# doogie_board.net
KiCad netlist of a schematic drawn in EAGLE
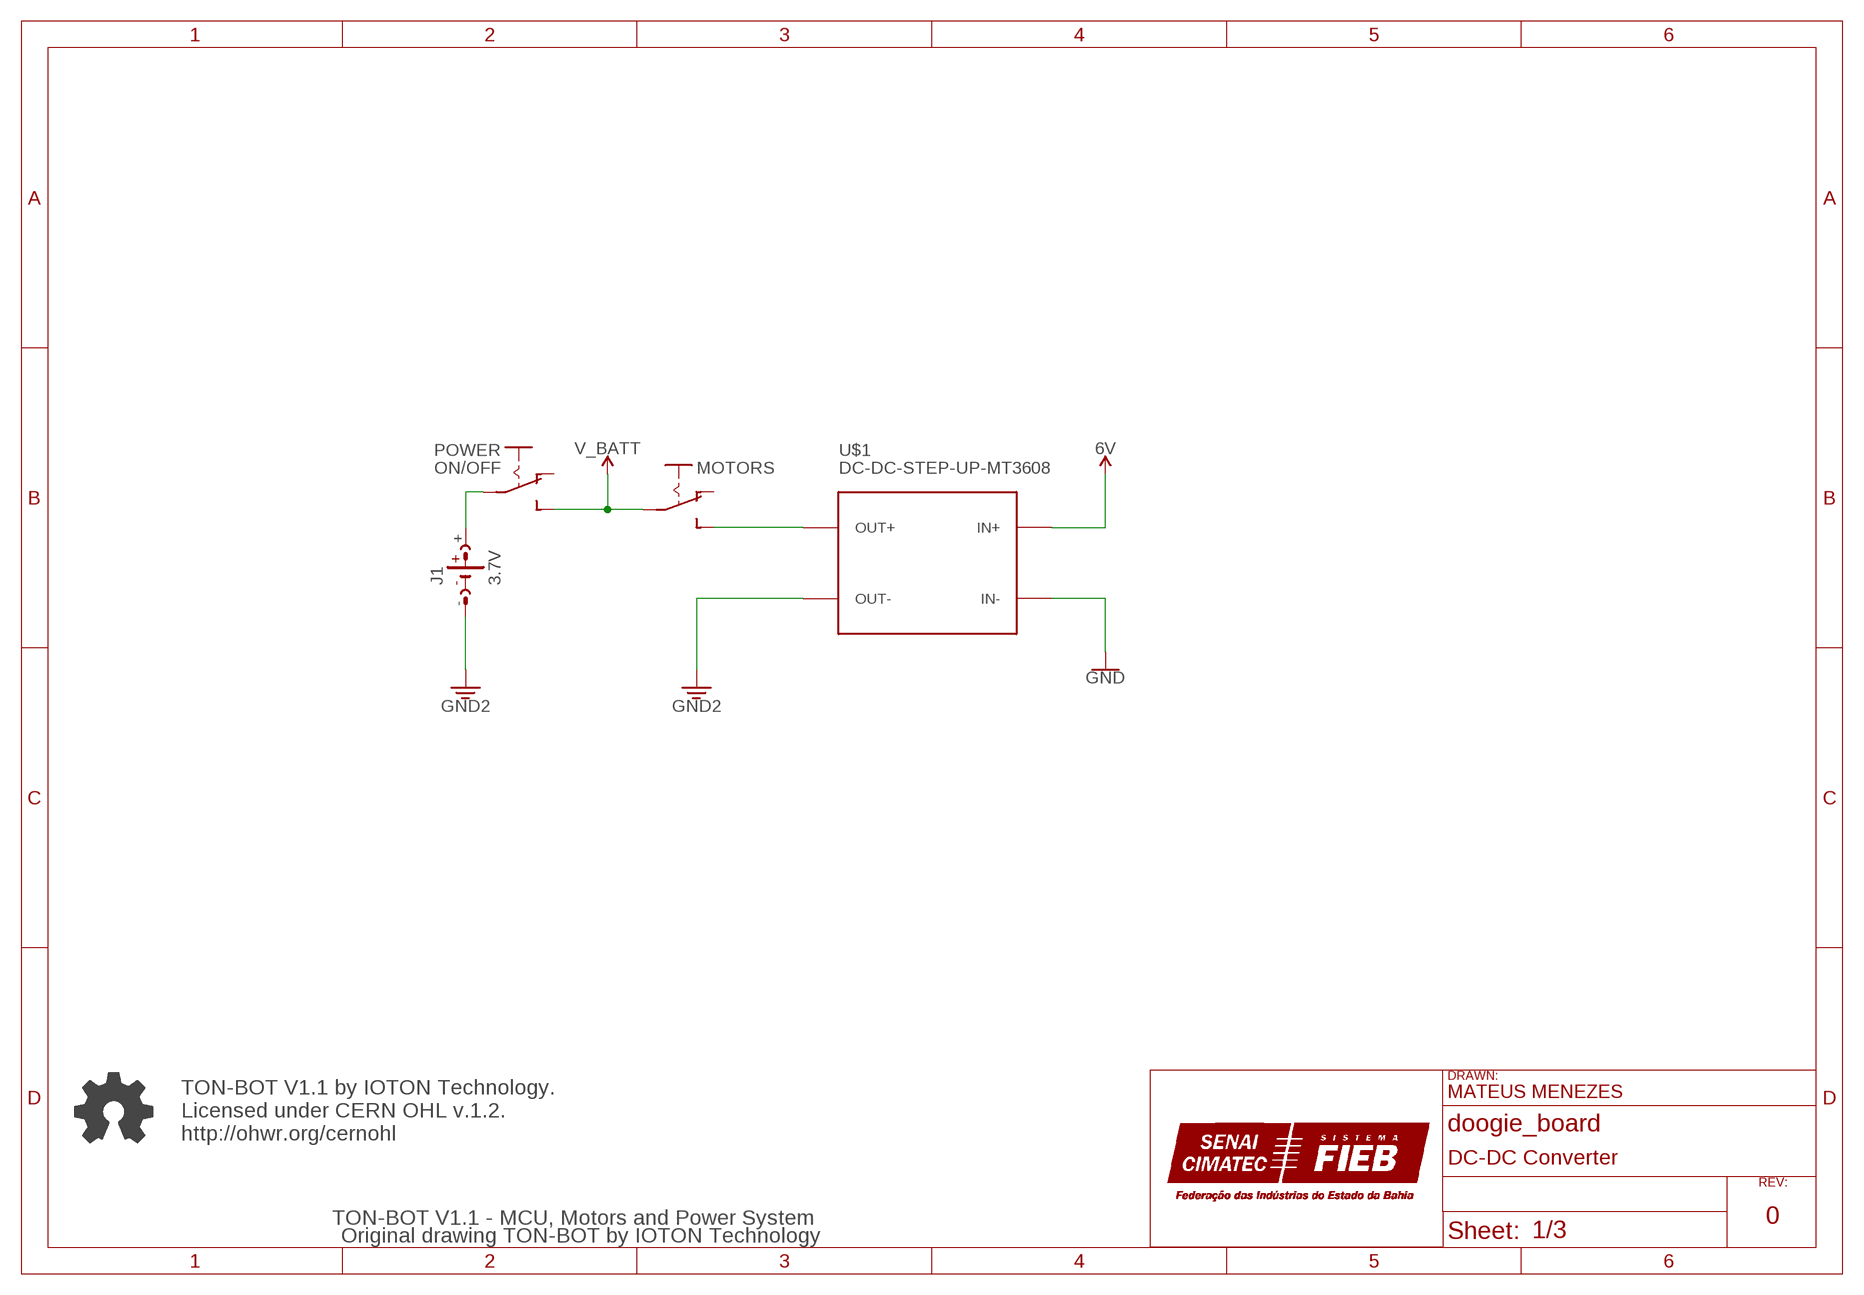
[diagram p0: schematic, sheet 1]
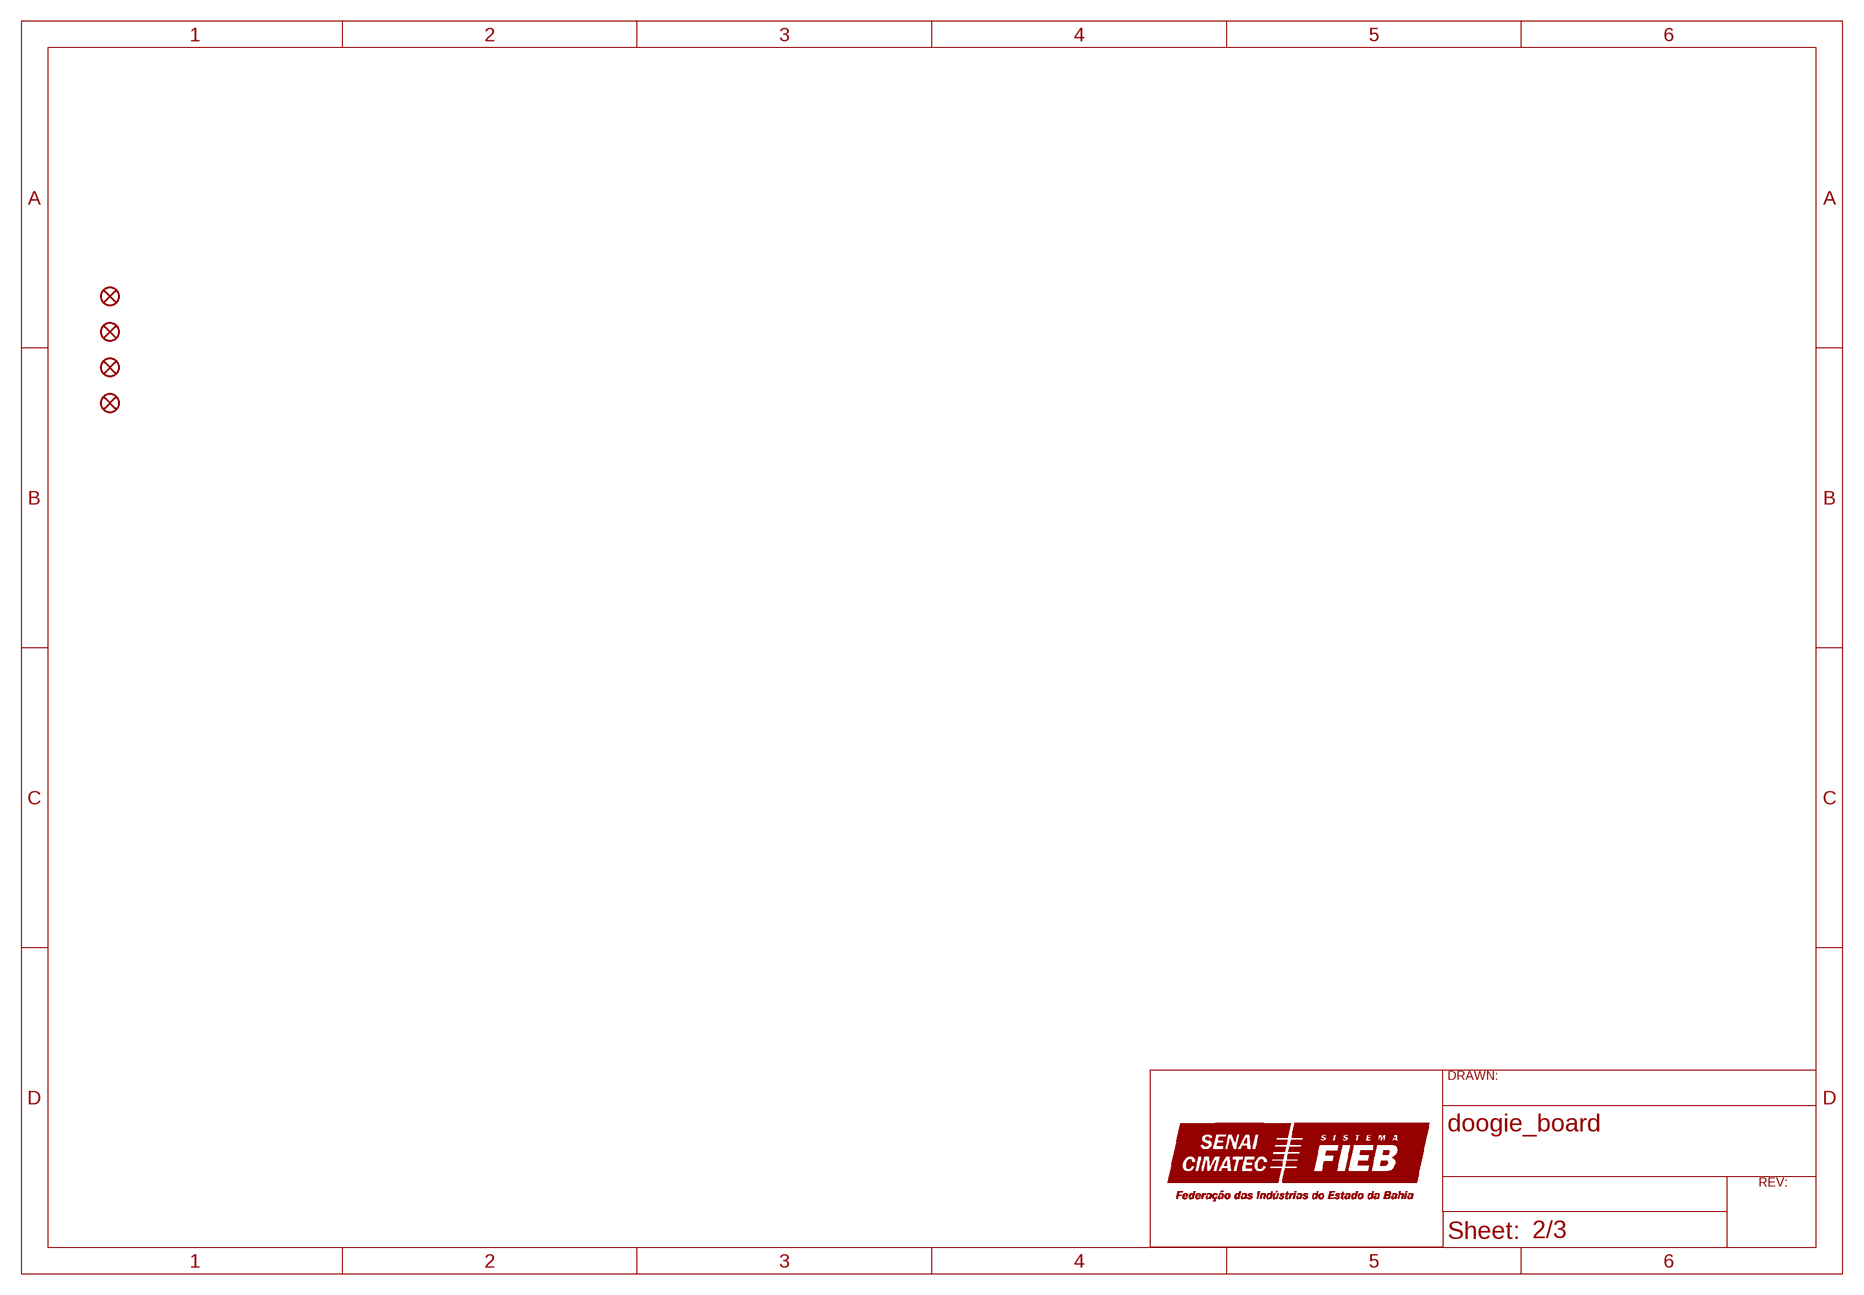
[diagram p1: schematic, sheet 2]
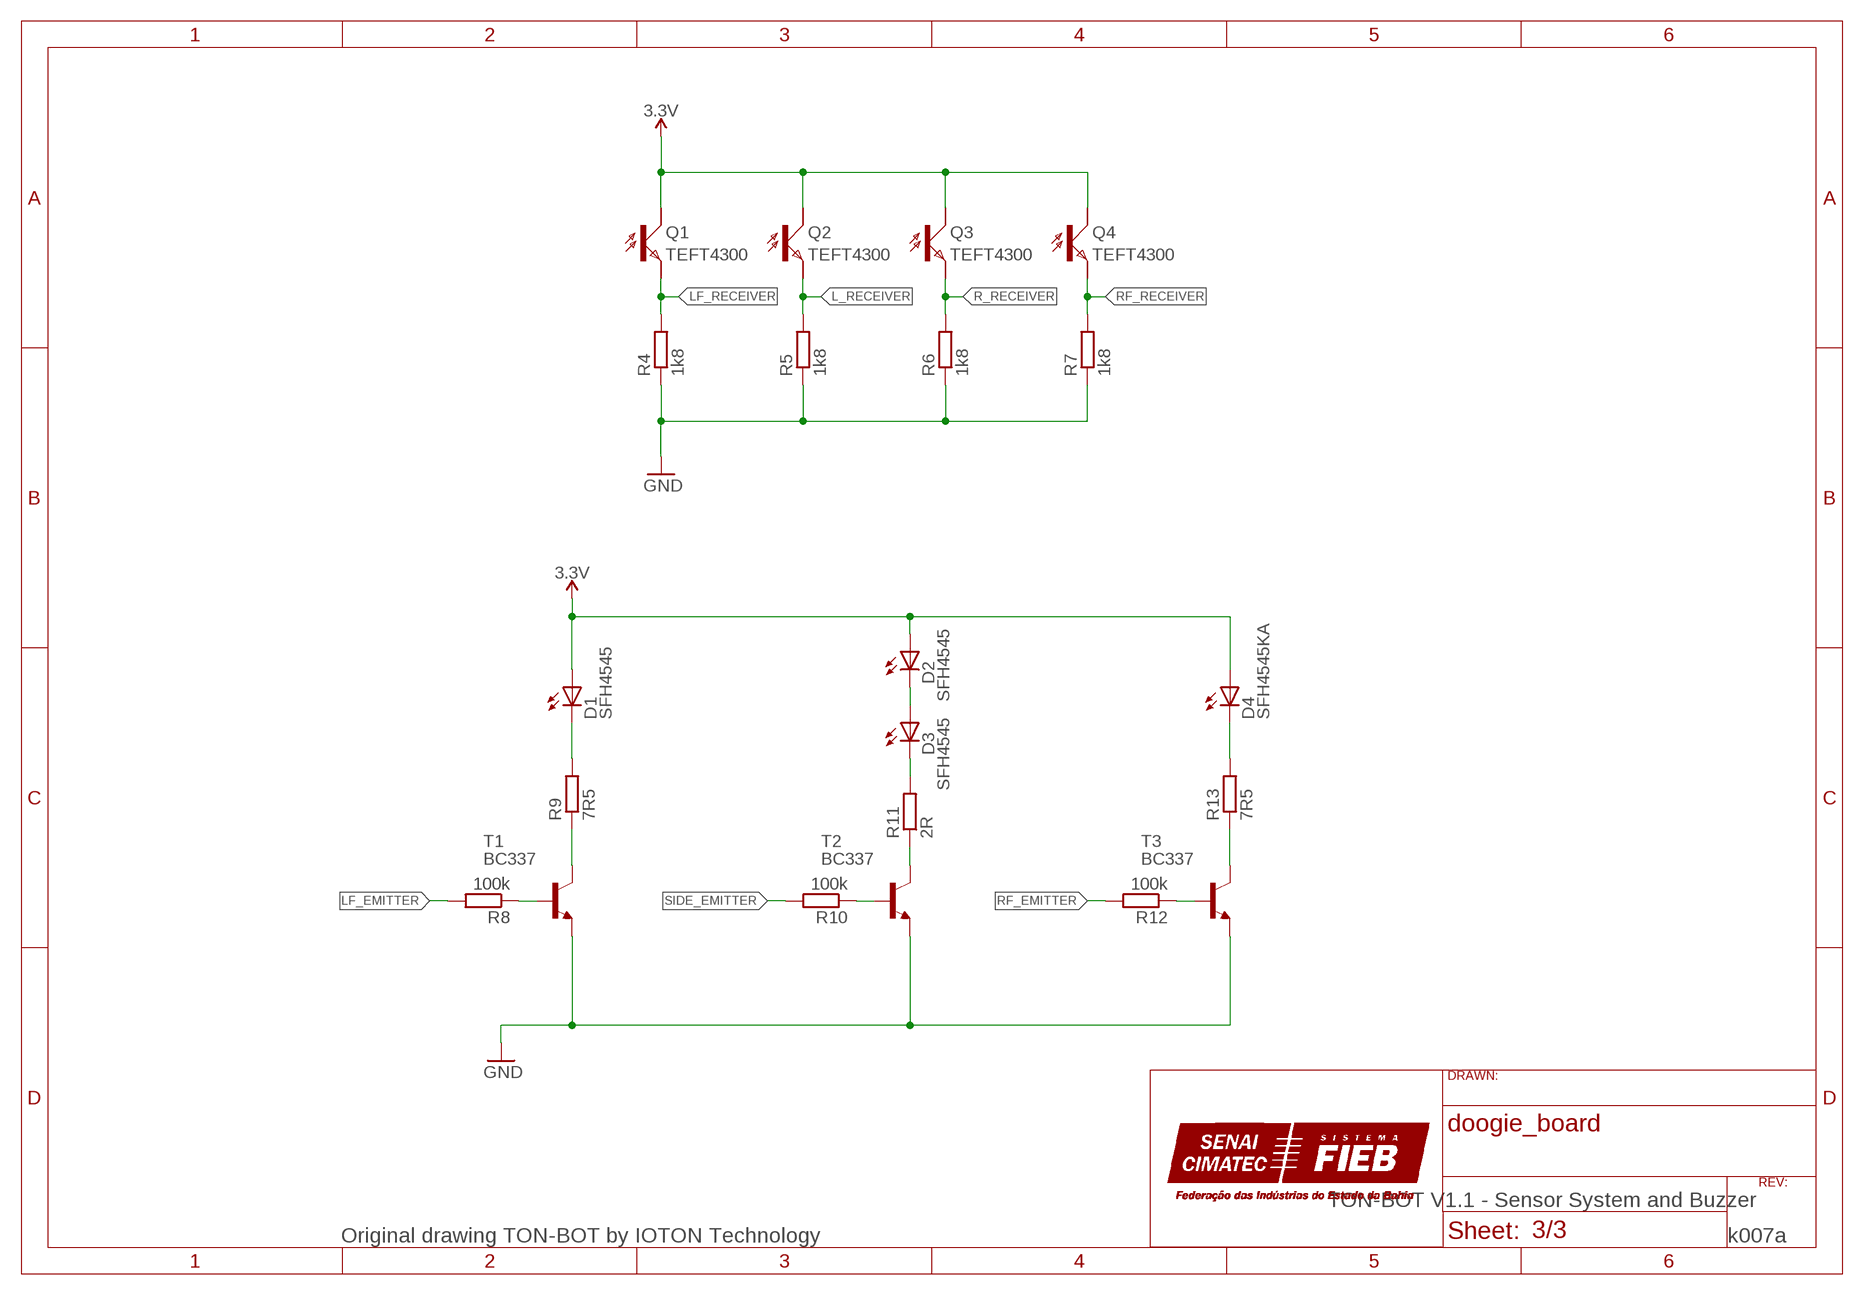
[diagram p2: schematic, sheet 3]

(export (version "E")
  (design (tool "Eeschema 10.0.6"))
  (components
    (comp (ref "JP1")
      (value "FIDUCIAL1X2")
      (footprint "eagle-import:FIDUCIAL-1X2")
      (libsource (lib "eagle-import") (part "FIDUCIAL1X2"))
    )
    (comp (ref "JP2")
      (value "FIDUCIAL1X2")
      (footprint "eagle-import:FIDUCIAL-1X2")
      (libsource (lib "eagle-import") (part "FIDUCIAL1X2"))
    )
    (comp (ref "JP3")
      (value "FIDUCIAL1X2")
      (footprint "eagle-import:FIDUCIAL-1X2")
      (libsource (lib "eagle-import") (part "FIDUCIAL1X2"))
    )
    (comp (ref "JP4")
      (value "FIDUCIAL1X2")
      (footprint "eagle-import:FIDUCIAL-1X2")
      (libsource (lib "eagle-import") (part "FIDUCIAL1X2"))
    )
    (comp (ref "U$3")
      (value "FRAME_A4P")
      (footprint "eagle-import:FRAME_A4P")
      (libsource (lib "eagle-import") (part "FRAME_A4P"))
    )
    (comp (ref "J1")
      (value "3.7V")
      (footprint "eagle-import:BATTERY")
      (libsource (lib "eagle-import") (part "BATTERY"))
    )
    (comp (ref "MOTORS")
      (value "SWITCHS")
      (footprint "eagle-import:SWITCH")
      (libsource (lib "eagle-import") (part "SWITCHS"))
    )
    (comp (ref "POWER")
      (value "ON/OFF")
      (footprint "eagle-import:SWITCH")
      (libsource (lib "eagle-import") (part "SWITCHS"))
    )
    (comp (ref "U$1")
      (value "DC-DC-STEP-UP-MT3608")
      (footprint "eagle-import:DC-DC-STEP-UP-MT3608")
      (libsource (lib "eagle-import") (part "DC-DC-STEP-UP-MT3608"))
    )
    (comp (ref "U$2")
      (value "FRAME_A4P")
      (footprint "eagle-import:FRAME_A4P")
      (fields
        (field (name "DESIGNER_NAME") "MATEUS MENEZES")
        (field (name "PAGE_DESCRIPTION") "DC-DC Converter")
        (field (name "REV_NUMBER") "0")
      )
      (libsource (lib "eagle-import") (part "FRAME_A4P"))
    )
    (comp (ref "D1")
      (value "SFH4545")
      (footprint "eagle-import:SFH4545-AK")
      (libsource (lib "eagle-import") (part "SFH4545AK"))
    )
    (comp (ref "D2")
      (value "SFH4545")
      (footprint "eagle-import:SFH4545-KA")
      (libsource (lib "eagle-import") (part "SFH4545KA"))
    )
    (comp (ref "D3")
      (value "SFH4545")
      (footprint "eagle-import:SFH4545-KA")
      (libsource (lib "eagle-import") (part "SFH4545KA"))
    )
    (comp (ref "D4")
      (value "SFH4545KA")
      (footprint "eagle-import:SFH4545-KA")
      (libsource (lib "eagle-import") (part "SFH4545KA"))
    )
    (comp (ref "Q1")
      (value "TEFT4300")
      (footprint "eagle-import:TEFT4300-CE")
      (libsource (lib "eagle-import") (part "TEFT4300CE"))
    )
    (comp (ref "Q2")
      (value "TEFT4300")
      (footprint "eagle-import:TEFT4300-EC")
      (libsource (lib "eagle-import") (part "TEFT4300EC"))
    )
    (comp (ref "Q3")
      (value "TEFT4300")
      (footprint "eagle-import:TEFT4300-CE")
      (libsource (lib "eagle-import") (part "TEFT4300CE"))
    )
    (comp (ref "Q4")
      (value "TEFT4300")
      (footprint "eagle-import:TEFT4300-EC")
      (libsource (lib "eagle-import") (part "TEFT4300EC"))
    )
    (comp (ref "R4")
      (value "1k8")
      (footprint "eagle-import:0204_7")
      (libsource (lib "eagle-import") (part "R-EU_0204/7"))
    )
    (comp (ref "R5")
      (value "1k8")
      (footprint "eagle-import:0204_7")
      (libsource (lib "eagle-import") (part "R-EU_0204/7"))
    )
    (comp (ref "R6")
      (value "1k8")
      (footprint "eagle-import:0204_7")
      (libsource (lib "eagle-import") (part "R-EU_0204/7"))
    )
    (comp (ref "R7")
      (value "1k8")
      (footprint "eagle-import:0204_7")
      (libsource (lib "eagle-import") (part "R-EU_0204/7"))
    )
    (comp (ref "R8")
      (value "100k")
      (footprint "eagle-import:0204_7")
      (libsource (lib "eagle-import") (part "R-EU_0204/7"))
    )
    (comp (ref "R9")
      (value "7R5")
      (footprint "eagle-import:0204_7")
      (libsource (lib "eagle-import") (part "R-EU_0204/7"))
    )
    (comp (ref "R10")
      (value "100k")
      (footprint "eagle-import:0204_7")
      (libsource (lib "eagle-import") (part "R-EU_0204/7"))
    )
    (comp (ref "R11")
      (value "2R")
      (footprint "eagle-import:0204_7")
      (libsource (lib "eagle-import") (part "R-EU_0204/7"))
    )
    (comp (ref "R12")
      (value "100k")
      (footprint "eagle-import:0204_7")
      (libsource (lib "eagle-import") (part "R-EU_0204/7"))
    )
    (comp (ref "R13")
      (value "7R5")
      (footprint "eagle-import:0204_7")
      (libsource (lib "eagle-import") (part "R-EU_0204/7"))
    )
    (comp (ref "T1")
      (value "BC337")
      (footprint "eagle-import:TO92")
      (libsource (lib "eagle-import") (part "BC337"))
    )
    (comp (ref "T2")
      (value "BC337")
      (footprint "eagle-import:TO92")
      (libsource (lib "eagle-import") (part "BC337"))
    )
    (comp (ref "T3")
      (value "BC337")
      (footprint "eagle-import:TO92")
      (libsource (lib "eagle-import") (part "BC337"))
    )
    (comp (ref "U$4")
      (value "FRAME_A4P")
      (footprint "eagle-import:FRAME_A4P")
      (libsource (lib "eagle-import") (part "FRAME_A4P"))
    )
  )
  (nets
    (net (code "1") (name "3.3V") (class "Default")
      (node (ref "D1") (pin "A") (pinfunction "A_A") (pintype "passive"))
      (node (ref "D2") (pin "A") (pinfunction "A_A") (pintype "passive"))
      (node (ref "D4") (pin "A") (pinfunction "A_A") (pintype "passive"))
      (node (ref "J1") (pin "-") (pinfunction "-_-") (pintype "passive"))
      (node (ref "Q1") (pin "C") (pinfunction "C_C") (pintype "passive"))
      (node (ref "Q2") (pin "C") (pinfunction "C_C") (pintype "passive"))
      (node (ref "Q3") (pin "C") (pinfunction "C_C") (pintype "passive"))
      (node (ref "Q4") (pin "C") (pinfunction "C_C") (pintype "passive"))
      (node (ref "U$1") (pin "OUT-") (pinfunction "OUT-_OUT-") (pintype "bidirectional"))
    )
    (net (code "2") (name "6V") (class "Default")
      (node (ref "U$1") (pin "IN+") (pinfunction "IN+_IN+") (pintype "bidirectional"))
    )
    (net (code "3") (name "GND") (class "Default")
      (node (ref "R4") (pin "1") (pinfunction "1_1") (pintype "passive"))
      (node (ref "R5") (pin "1") (pinfunction "1_1") (pintype "passive"))
      (node (ref "R6") (pin "1") (pinfunction "1_1") (pintype "passive"))
      (node (ref "R7") (pin "1") (pinfunction "1_1") (pintype "passive"))
      (node (ref "T1") (pin "1") (pinfunction "E_1") (pintype "passive"))
      (node (ref "T2") (pin "1") (pinfunction "E_1") (pintype "passive"))
      (node (ref "T3") (pin "1") (pinfunction "E_1") (pintype "passive"))
      (node (ref "U$1") (pin "IN-") (pinfunction "IN-_IN-") (pintype "bidirectional"))
    )
    (net (code "4") (name "LF_EMITTER") (class "Default")
      (node (ref "R8") (pin "2") (pinfunction "2_2") (pintype "passive"))
    )
    (net (code "5") (name "LF_RECEIVER") (class "Default")
      (node (ref "Q1") (pin "E") (pinfunction "E_E") (pintype "passive"))
      (node (ref "R4") (pin "2") (pinfunction "2_2") (pintype "passive"))
    )
    (net (code "6") (name "L_RECEIVER") (class "Default")
      (node (ref "Q2") (pin "E") (pinfunction "E_E") (pintype "passive"))
      (node (ref "R5") (pin "2") (pinfunction "2_2") (pintype "passive"))
    )
    (net (code "7") (name "Net-(D1-PadK)") (class "Default")
      (node (ref "D1") (pin "K") (pinfunction "K_K") (pintype "passive"))
      (node (ref "R9") (pin "2") (pinfunction "2_2") (pintype "passive"))
    )
    (net (code "8") (name "Net-(D2-PadK)") (class "Default")
      (node (ref "D2") (pin "K") (pinfunction "K_K") (pintype "passive"))
      (node (ref "D3") (pin "A") (pinfunction "A_A") (pintype "passive"))
    )
    (net (code "9") (name "Net-(D3-PadK)") (class "Default")
      (node (ref "D3") (pin "K") (pinfunction "K_K") (pintype "passive"))
      (node (ref "R11") (pin "2") (pinfunction "2_2") (pintype "passive"))
    )
    (net (code "10") (name "Net-(D4-PadK)") (class "Default")
      (node (ref "D4") (pin "K") (pinfunction "K_K") (pintype "passive"))
      (node (ref "R13") (pin "2") (pinfunction "2_2") (pintype "passive"))
    )
    (net (code "11") (name "Net-(J1-Pad+)") (class "Default")
      (node (ref "J1") (pin "+") (pinfunction "+_+") (pintype "passive"))
      (node (ref "POWER") (pin "P") (pinfunction "P_P") (pintype "passive"))
    )
    (net (code "12") (name "Net-(MOTORS-PadS)") (class "Default")
      (node (ref "MOTORS") (pin "S") (pinfunction "S_S") (pintype "passive"))
      (node (ref "U$1") (pin "OUT+") (pinfunction "OUT+_OUT+") (pintype "bidirectional"))
    )
    (net (code "13") (name "Net-(T1-B)") (class "Default")
      (node (ref "R8") (pin "1") (pinfunction "1_1") (pintype "passive"))
      (node (ref "T1") (pin "2") (pinfunction "B_2") (pintype "passive"))
    )
    (net (code "14") (name "Net-(T1-C)") (class "Default")
      (node (ref "R9") (pin "1") (pinfunction "1_1") (pintype "passive"))
      (node (ref "T1") (pin "3") (pinfunction "C_3") (pintype "passive"))
    )
    (net (code "15") (name "Net-(T2-B)") (class "Default")
      (node (ref "R10") (pin "1") (pinfunction "1_1") (pintype "passive"))
      (node (ref "T2") (pin "2") (pinfunction "B_2") (pintype "passive"))
    )
    (net (code "16") (name "Net-(T2-C)") (class "Default")
      (node (ref "R11") (pin "1") (pinfunction "1_1") (pintype "passive"))
      (node (ref "T2") (pin "3") (pinfunction "C_3") (pintype "passive"))
    )
    (net (code "17") (name "Net-(T3-B)") (class "Default")
      (node (ref "R12") (pin "1") (pinfunction "1_1") (pintype "passive"))
      (node (ref "T3") (pin "2") (pinfunction "B_2") (pintype "passive"))
    )
    (net (code "18") (name "Net-(T3-C)") (class "Default")
      (node (ref "R13") (pin "1") (pinfunction "1_1") (pintype "passive"))
      (node (ref "T3") (pin "3") (pinfunction "C_3") (pintype "passive"))
    )
    (net (code "19") (name "RF_EMITTER") (class "Default")
      (node (ref "R12") (pin "2") (pinfunction "2_2") (pintype "passive"))
    )
    (net (code "20") (name "RF_RECEIVER") (class "Default")
      (node (ref "Q4") (pin "E") (pinfunction "E_E") (pintype "passive"))
      (node (ref "R7") (pin "2") (pinfunction "2_2") (pintype "passive"))
    )
    (net (code "21") (name "R_RECEIVER") (class "Default")
      (node (ref "Q3") (pin "E") (pinfunction "E_E") (pintype "passive"))
      (node (ref "R6") (pin "2") (pinfunction "2_2") (pintype "passive"))
    )
    (net (code "22") (name "SIDE_EMITTER") (class "Default")
      (node (ref "R10") (pin "2") (pinfunction "2_2") (pintype "passive"))
    )
    (net (code "23") (name "V_BATT") (class "Default")
      (node (ref "MOTORS") (pin "P") (pinfunction "P_P") (pintype "passive"))
      (node (ref "POWER") (pin "S") (pinfunction "S_S") (pintype "passive"))
    )
    (net (code "24") (name "unconnected-(MOTORS-PadO)") (class "Default")
      (node (ref "MOTORS") (pin "O") (pinfunction "O_O") (pintype "passive"))
    )
    (net (code "25") (name "unconnected-(POWER-PadO)") (class "Default")
      (node (ref "POWER") (pin "O") (pinfunction "O_O") (pintype "passive"))
    )
  )
)
